# main_multicore.net
KiCad netlist of a schematic drawn in EAGLE
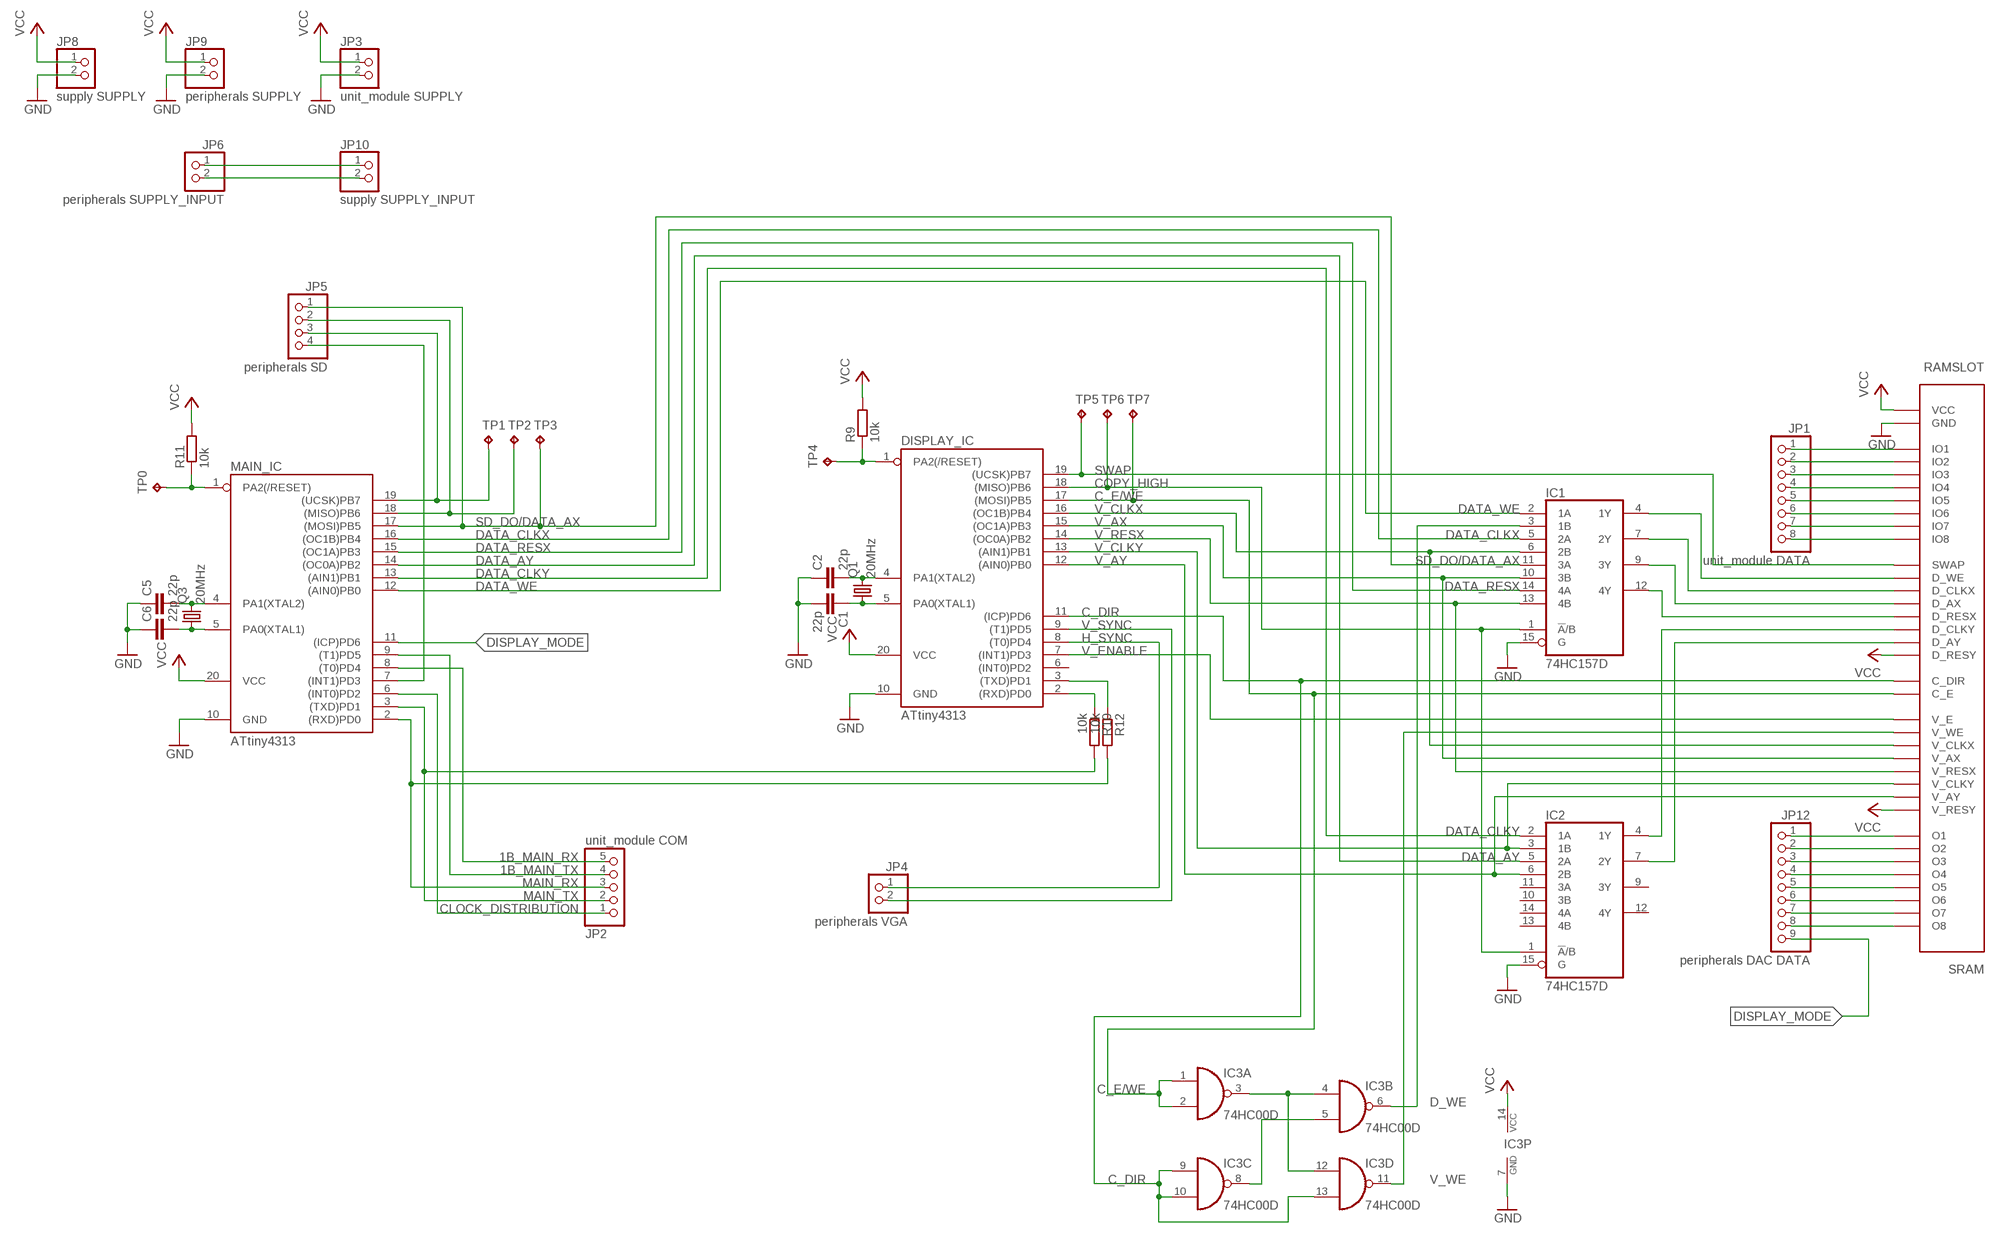
[diagram p0: schematic, sheet 1]

(export (version "E")
  (design (tool "Eeschema 10.0.6"))
  (components
    (comp (ref "C1")
      (value "22p")
      (footprint "eagle-import:C0402")
      (libsource (lib "eagle-import") (part "C-EUC0402"))
    )
    (comp (ref "C2")
      (value "22p")
      (footprint "eagle-import:C0402")
      (libsource (lib "eagle-import") (part "C-EUC0402"))
    )
    (comp (ref "C5")
      (value "22p")
      (footprint "eagle-import:C0402")
      (libsource (lib "eagle-import") (part "C-EUC0402"))
    )
    (comp (ref "C6")
      (value "22p")
      (footprint "eagle-import:C0402")
      (libsource (lib "eagle-import") (part "C-EUC0402"))
    )
    (comp (ref "DISPLAY_IC")
      (value "ATtiny4313")
      (footprint "eagle-import:SO20L$")
      (libsource (lib "eagle-import") (part "TINY2313-S"))
    )
    (comp (ref "IC1")
      (value "74HC157D")
      (footprint "eagle-import:SO16")
      (libsource (lib "eagle-import") (part "74157DHC"))
    )
    (comp (ref "IC2")
      (value "74HC157D")
      (footprint "eagle-import:SO16")
      (libsource (lib "eagle-import") (part "74157DHC"))
    )
    (comp (ref "IC3")
      (value "74HC00D")
      (footprint "eagle-import:SO14")
      (libsource (lib "eagle-import") (part "7400DHC"))
    )
    (comp (ref "JP1")
      (value "unit_module DATA")
      (footprint "eagle-import:1X08")
      (libsource (lib "eagle-import") (part "PINHD-1X8"))
    )
    (comp (ref "JP2")
      (value "unit_module COM")
      (footprint "eagle-import:1X05")
      (libsource (lib "eagle-import") (part "PINHD-1X5"))
    )
    (comp (ref "JP3")
      (value "unit_module SUPPLY")
      (footprint "eagle-import:1X02")
      (libsource (lib "eagle-import") (part "PINHD-1X2"))
    )
    (comp (ref "JP4")
      (value "peripherals VGA")
      (footprint "eagle-import:1X02")
      (libsource (lib "eagle-import") (part "PINHD-1X2"))
    )
    (comp (ref "JP5")
      (value "peripherals SD")
      (footprint "eagle-import:1X04")
      (libsource (lib "eagle-import") (part "PINHD-1X4"))
    )
    (comp (ref "JP6")
      (value "peripherals SUPPLY_INPUT")
      (footprint "eagle-import:1X02")
      (libsource (lib "eagle-import") (part "PINHD-1X2"))
    )
    (comp (ref "JP8")
      (value "supply SUPPLY")
      (footprint "eagle-import:1X02")
      (libsource (lib "eagle-import") (part "PINHD-1X2"))
    )
    (comp (ref "JP9")
      (value "peripherals SUPPLY")
      (footprint "eagle-import:1X02")
      (libsource (lib "eagle-import") (part "PINHD-1X2"))
    )
    (comp (ref "JP10")
      (value "supply SUPPLY_INPUT")
      (footprint "eagle-import:1X02")
      (libsource (lib "eagle-import") (part "PINHD-1X2"))
    )
    (comp (ref "JP12")
      (value "peripherals DAC DATA")
      (footprint "eagle-import:1X09")
      (libsource (lib "eagle-import") (part "PINHD-1X9"))
    )
    (comp (ref "MAIN_IC")
      (value "ATtiny4313")
      (footprint "eagle-import:SO20L$")
      (libsource (lib "eagle-import") (part "TINY2313-S"))
    )
    (comp (ref "Q1")
      (value "20MHz")
      (footprint "eagle-import:MC-405")
      (libsource (lib "eagle-import") (part "MC-405"))
    )
    (comp (ref "Q3")
      (value "20MHz")
      (footprint "eagle-import:MC-405")
      (libsource (lib "eagle-import") (part "MC-405"))
    )
    (comp (ref "R9")
      (value "10k")
      (footprint "eagle-import:R0603")
      (libsource (lib "eagle-import") (part "R-EU_R0603"))
    )
    (comp (ref "R10")
      (value "10k")
      (footprint "eagle-import:R0603")
      (libsource (lib "eagle-import") (part "R-EU_R0603"))
    )
    (comp (ref "R11")
      (value "10k")
      (footprint "eagle-import:R0603")
      (libsource (lib "eagle-import") (part "R-EU_R0603"))
    )
    (comp (ref "R12")
      (value "10k")
      (footprint "eagle-import:R0603")
      (libsource (lib "eagle-import") (part "R-EU_R0603"))
    )
    (comp (ref "RAMSLOT")
      (value "SRAM")
      (footprint "eagle-import:SLOT")
      (libsource (lib "eagle-import") (part "SLOT"))
    )
    (comp (ref "TP0")
      (value "TPB1,27")
      (footprint "eagle-import:B1,27")
      (libsource (lib "eagle-import") (part "TPB1,27"))
    )
    (comp (ref "TP1")
      (value "TPB1,27")
      (footprint "eagle-import:B1,27")
      (libsource (lib "eagle-import") (part "TPB1,27"))
    )
    (comp (ref "TP2")
      (value "TPB1,27")
      (footprint "eagle-import:B1,27")
      (libsource (lib "eagle-import") (part "TPB1,27"))
    )
    (comp (ref "TP3")
      (value "TPB1,27")
      (footprint "eagle-import:B1,27")
      (libsource (lib "eagle-import") (part "TPB1,27"))
    )
    (comp (ref "TP4")
      (value "TPB1,27")
      (footprint "eagle-import:B1,27")
      (libsource (lib "eagle-import") (part "TPB1,27"))
    )
    (comp (ref "TP5")
      (value "TPB1,27")
      (footprint "eagle-import:B1,27")
      (libsource (lib "eagle-import") (part "TPB1,27"))
    )
    (comp (ref "TP6")
      (value "TPB1,27")
      (footprint "eagle-import:B1,27")
      (libsource (lib "eagle-import") (part "TPB1,27"))
    )
    (comp (ref "TP7")
      (value "TPB1,27")
      (footprint "eagle-import:B1,27")
      (libsource (lib "eagle-import") (part "TPB1,27"))
    )
  )
  (nets
    (net (code "1") (name "/1B_MAIN_RX") (class "Default")
      (node (ref "JP2") (pin "5") (pinfunction "5_5") (pintype "passive"))
      (node (ref "MAIN_IC") (pin "8") (pinfunction "(T0)PD4_8") (pintype "bidirectional"))
    )
    (net (code "2") (name "/1B_MAIN_TX") (class "Default")
      (node (ref "JP2") (pin "4") (pinfunction "4_4") (pintype "passive"))
      (node (ref "MAIN_IC") (pin "9") (pinfunction "(T1)PD5_9") (pintype "bidirectional"))
    )
    (net (code "3") (name "/CLOCK_DISTRIBUTION") (class "Default")
      (node (ref "JP2") (pin "1") (pinfunction "1_1") (pintype "passive"))
      (node (ref "MAIN_IC") (pin "6") (pinfunction "(INT0)PD2_6") (pintype "bidirectional"))
    )
    (net (code "4") (name "/COPY_HIGH") (class "Default")
      (node (ref "DISPLAY_IC") (pin "18") (pinfunction "(MISO)PB6_18") (pintype "bidirectional"))
      (node (ref "IC1") (pin "1") (pinfunction "~{A}/B_1") (pintype "input"))
      (node (ref "IC2") (pin "1") (pinfunction "~{A}/B_1") (pintype "input"))
      (node (ref "TP6") (pin "TP") (pinfunction "TP_TP") (pintype "input"))
    )
    (net (code "5") (name "/C_DIR") (class "Default")
      (node (ref "DISPLAY_IC") (pin "11") (pinfunction "(ICP)PD6_11") (pintype "bidirectional"))
      (node (ref "IC3") (pin "10") (pinfunction "I1_10") (pintype "input"))
      (node (ref "IC3") (pin "13") (pinfunction "I1_13") (pintype "input"))
      (node (ref "IC3") (pin "9") (pinfunction "I0_9") (pintype "input"))
      (node (ref "RAMSLOT") (pin "C_DIR") (pinfunction "C_DIR_C_DIR") (pintype "bidirectional"))
    )
    (net (code "6") (name "/C_E{slash}WE") (class "Default")
      (node (ref "DISPLAY_IC") (pin "17") (pinfunction "(MOSI)PB5_17") (pintype "bidirectional"))
      (node (ref "IC3") (pin "1") (pinfunction "I0_1") (pintype "input"))
      (node (ref "IC3") (pin "2") (pinfunction "I1_2") (pintype "input"))
      (node (ref "RAMSLOT") (pin "C_E") (pinfunction "C_E_C_E") (pintype "bidirectional"))
      (node (ref "TP7") (pin "TP") (pinfunction "TP_TP") (pintype "input"))
    )
    (net (code "7") (name "/DATA_AY") (class "Default")
      (node (ref "IC2") (pin "5") (pinfunction "2A_5") (pintype "input"))
      (node (ref "MAIN_IC") (pin "14") (pinfunction "(OC0A)PB2_14") (pintype "bidirectional"))
    )
    (net (code "8") (name "/DATA_CLKX") (class "Default")
      (node (ref "IC1") (pin "5") (pinfunction "2A_5") (pintype "input"))
      (node (ref "MAIN_IC") (pin "16") (pinfunction "(OC1B)PB4_16") (pintype "bidirectional"))
    )
    (net (code "9") (name "/DATA_CLKY") (class "Default")
      (node (ref "IC2") (pin "2") (pinfunction "1A_2") (pintype "input"))
      (node (ref "MAIN_IC") (pin "13") (pinfunction "(AIN1)PB1_13") (pintype "bidirectional"))
    )
    (net (code "10") (name "/DATA_RESX") (class "Default")
      (node (ref "IC1") (pin "14") (pinfunction "4A_14") (pintype "input"))
      (node (ref "MAIN_IC") (pin "15") (pinfunction "(OC1A)PB3_15") (pintype "bidirectional"))
    )
    (net (code "11") (name "/DATA_WE") (class "Default")
      (node (ref "IC1") (pin "2") (pinfunction "1A_2") (pintype "input"))
      (node (ref "MAIN_IC") (pin "12") (pinfunction "(AIN0)PB0_12") (pintype "bidirectional"))
    )
    (net (code "12") (name "/D_WE") (class "Default")
      (node (ref "IC1") (pin "3") (pinfunction "1B_3") (pintype "input"))
      (node (ref "IC3") (pin "6") (pinfunction "O_6") (pintype "output"))
    )
    (net (code "13") (name "/H_SYNC") (class "Default")
      (node (ref "DISPLAY_IC") (pin "8") (pinfunction "(T0)PD4_8") (pintype "bidirectional"))
      (node (ref "JP4") (pin "1") (pinfunction "1_1") (pintype "passive"))
    )
    (net (code "14") (name "/MAIN_RX") (class "Default")
      (node (ref "JP2") (pin "3") (pinfunction "3_3") (pintype "passive"))
      (node (ref "MAIN_IC") (pin "2") (pinfunction "(RXD)PD0_2") (pintype "bidirectional"))
      (node (ref "R12") (pin "2") (pinfunction "2_2") (pintype "passive"))
    )
    (net (code "15") (name "/MAIN_TX") (class "Default")
      (node (ref "JP2") (pin "2") (pinfunction "2_2") (pintype "passive"))
      (node (ref "MAIN_IC") (pin "3") (pinfunction "(TXD)PD1_3") (pintype "bidirectional"))
      (node (ref "R10") (pin "2") (pinfunction "2_2") (pintype "passive"))
    )
    (net (code "16") (name "/SD_DO{slash}DATA_AX") (class "Default")
      (node (ref "IC1") (pin "11") (pinfunction "3A_11") (pintype "input"))
      (node (ref "JP5") (pin "1") (pinfunction "1_1") (pintype "passive"))
      (node (ref "MAIN_IC") (pin "17") (pinfunction "(MOSI)PB5_17") (pintype "bidirectional"))
      (node (ref "TP3") (pin "TP") (pinfunction "TP_TP") (pintype "input"))
    )
    (net (code "17") (name "/SWAP") (class "Default")
      (node (ref "DISPLAY_IC") (pin "19") (pinfunction "(UCSK)PB7_19") (pintype "bidirectional"))
      (node (ref "RAMSLOT") (pin "SWAP") (pinfunction "SWAP_SWAP") (pintype "bidirectional"))
      (node (ref "TP5") (pin "TP") (pinfunction "TP_TP") (pintype "input"))
    )
    (net (code "18") (name "/V_AX") (class "Default")
      (node (ref "DISPLAY_IC") (pin "15") (pinfunction "(OC1A)PB3_15") (pintype "bidirectional"))
      (node (ref "IC1") (pin "10") (pinfunction "3B_10") (pintype "input"))
      (node (ref "RAMSLOT") (pin "V_AX") (pinfunction "V_AX_V_AX") (pintype "bidirectional"))
    )
    (net (code "19") (name "/V_AY") (class "Default")
      (node (ref "DISPLAY_IC") (pin "12") (pinfunction "(AIN0)PB0_12") (pintype "bidirectional"))
      (node (ref "IC2") (pin "6") (pinfunction "2B_6") (pintype "input"))
      (node (ref "RAMSLOT") (pin "V_AY") (pinfunction "V_AY_V_AY") (pintype "bidirectional"))
    )
    (net (code "20") (name "/V_CLKX") (class "Default")
      (node (ref "DISPLAY_IC") (pin "16") (pinfunction "(OC1B)PB4_16") (pintype "bidirectional"))
      (node (ref "IC1") (pin "6") (pinfunction "2B_6") (pintype "input"))
      (node (ref "RAMSLOT") (pin "V_CLKX") (pinfunction "V_CLKX_V_CLKX") (pintype "bidirectional"))
    )
    (net (code "21") (name "/V_CLKY") (class "Default")
      (node (ref "DISPLAY_IC") (pin "13") (pinfunction "(AIN1)PB1_13") (pintype "bidirectional"))
      (node (ref "IC2") (pin "3") (pinfunction "1B_3") (pintype "input"))
      (node (ref "RAMSLOT") (pin "V_CLKY") (pinfunction "V_CLKY_V_CLKY") (pintype "bidirectional"))
    )
    (net (code "22") (name "/V_ENABLE") (class "Default")
      (node (ref "DISPLAY_IC") (pin "7") (pinfunction "(INT1)PD3_7") (pintype "bidirectional"))
      (node (ref "RAMSLOT") (pin "V_E") (pinfunction "V_E_V_E") (pintype "bidirectional"))
    )
    (net (code "23") (name "/V_RESX") (class "Default")
      (node (ref "DISPLAY_IC") (pin "14") (pinfunction "(OC0A)PB2_14") (pintype "bidirectional"))
      (node (ref "IC1") (pin "13") (pinfunction "4B_13") (pintype "input"))
      (node (ref "RAMSLOT") (pin "V_RESX") (pinfunction "V_RESX_V_RESX") (pintype "bidirectional"))
    )
    (net (code "24") (name "/V_SYNC") (class "Default")
      (node (ref "DISPLAY_IC") (pin "9") (pinfunction "(T1)PD5_9") (pintype "bidirectional"))
      (node (ref "JP4") (pin "2") (pinfunction "2_2") (pintype "passive"))
    )
    (net (code "25") (name "/V_WE") (class "Default")
      (node (ref "IC3") (pin "11") (pinfunction "O_11") (pintype "output"))
      (node (ref "RAMSLOT") (pin "V_WE") (pinfunction "V_WE_V_WE") (pintype "bidirectional"))
    )
    (net (code "26") (name "DISPLAY_MODE") (class "Default")
      (node (ref "JP12") (pin "9") (pinfunction "9_9") (pintype "passive"))
      (node (ref "MAIN_IC") (pin "11") (pinfunction "(ICP)PD6_11") (pintype "bidirectional"))
    )
    (net (code "27") (name "GND") (class "Default")
      (node (ref "C1") (pin "2") (pinfunction "2_2") (pintype "passive"))
      (node (ref "C2") (pin "1") (pinfunction "1_1") (pintype "passive"))
      (node (ref "C5") (pin "1") (pinfunction "1_1") (pintype "passive"))
      (node (ref "C6") (pin "1") (pinfunction "1_1") (pintype "passive"))
      (node (ref "DISPLAY_IC") (pin "10") (pinfunction "GND_10") (pintype "power_in"))
      (node (ref "IC1") (pin "15") (pinfunction "G_15") (pintype "input"))
      (node (ref "IC2") (pin "15") (pinfunction "G_15") (pintype "input"))
      (node (ref "IC3") (pin "7") (pinfunction "GND_7") (pintype "power_in"))
      (node (ref "JP3") (pin "2") (pinfunction "2_2") (pintype "passive"))
      (node (ref "JP8") (pin "2") (pinfunction "2_2") (pintype "passive"))
      (node (ref "JP9") (pin "2") (pinfunction "2_2") (pintype "passive"))
      (node (ref "MAIN_IC") (pin "10") (pinfunction "GND_10") (pintype "power_in"))
      (node (ref "RAMSLOT") (pin "GND") (pinfunction "GND_GND") (pintype "bidirectional"))
    )
    (net (code "28") (name "Net-(DISPLAY_IC-(RXD)PD0)") (class "Default")
      (node (ref "DISPLAY_IC") (pin "2") (pinfunction "(RXD)PD0_2") (pintype "bidirectional"))
      (node (ref "R10") (pin "1") (pinfunction "1_1") (pintype "passive"))
    )
    (net (code "29") (name "Net-(DISPLAY_IC-(TXD)PD1)") (class "Default")
      (node (ref "DISPLAY_IC") (pin "3") (pinfunction "(TXD)PD1_3") (pintype "bidirectional"))
      (node (ref "R12") (pin "1") (pinfunction "1_1") (pintype "passive"))
    )
    (net (code "30") (name "Net-(DISPLAY_IC-PA0(XTAL1))") (class "Default")
      (node (ref "C1") (pin "1") (pinfunction "1_1") (pintype "passive"))
      (node (ref "DISPLAY_IC") (pin "5") (pinfunction "PA0(XTAL1)_5") (pintype "bidirectional"))
      (node (ref "Q1") (pin "1") (pinfunction "1_1") (pintype "passive"))
    )
    (net (code "31") (name "Net-(DISPLAY_IC-PA1(XTAL2))") (class "Default")
      (node (ref "C2") (pin "2") (pinfunction "2_2") (pintype "passive"))
      (node (ref "DISPLAY_IC") (pin "4") (pinfunction "PA1(XTAL2)_4") (pintype "bidirectional"))
      (node (ref "Q1") (pin "2") (pinfunction "2_2") (pintype "passive"))
    )
    (net (code "32") (name "Net-(DISPLAY_IC-PA2({slash}RESET))") (class "Default")
      (node (ref "DISPLAY_IC") (pin "1") (pinfunction "PA2(/RESET)_1") (pintype "input"))
      (node (ref "R9") (pin "1") (pinfunction "1_1") (pintype "passive"))
      (node (ref "TP4") (pin "TP") (pinfunction "TP_TP") (pintype "input"))
    )
    (net (code "33") (name "Net-(IC1A-1Y)") (class "Default")
      (node (ref "IC1") (pin "4") (pinfunction "1Y_4") (pintype "output"))
      (node (ref "RAMSLOT") (pin "D_WE") (pinfunction "D_WE_D_WE") (pintype "bidirectional"))
    )
    (net (code "34") (name "Net-(IC1A-2Y)") (class "Default")
      (node (ref "IC1") (pin "7") (pinfunction "2Y_7") (pintype "output"))
      (node (ref "RAMSLOT") (pin "D_CLKX") (pinfunction "D_CLKX_D_CLKX") (pintype "bidirectional"))
    )
    (net (code "35") (name "Net-(IC1A-3Y)") (class "Default")
      (node (ref "IC1") (pin "9") (pinfunction "3Y_9") (pintype "output"))
      (node (ref "RAMSLOT") (pin "D_AX") (pinfunction "D_AX_D_AX") (pintype "bidirectional"))
    )
    (net (code "36") (name "Net-(IC1A-4Y)") (class "Default")
      (node (ref "IC1") (pin "12") (pinfunction "4Y_12") (pintype "output"))
      (node (ref "RAMSLOT") (pin "D_RESX") (pinfunction "D_RESX_D_RESX") (pintype "bidirectional"))
    )
    (net (code "37") (name "Net-(IC2A-1Y)") (class "Default")
      (node (ref "IC2") (pin "4") (pinfunction "1Y_4") (pintype "output"))
      (node (ref "RAMSLOT") (pin "D_CLKY") (pinfunction "D_CLKY_D_CLKY") (pintype "bidirectional"))
    )
    (net (code "38") (name "Net-(IC2A-2Y)") (class "Default")
      (node (ref "IC2") (pin "7") (pinfunction "2Y_7") (pintype "output"))
      (node (ref "RAMSLOT") (pin "D_AY") (pinfunction "D_AY_D_AY") (pintype "bidirectional"))
    )
    (net (code "39") (name "Net-(IC3A-O)") (class "Default")
      (node (ref "IC3") (pin "12") (pinfunction "I0_12") (pintype "input"))
      (node (ref "IC3") (pin "3") (pinfunction "O_3") (pintype "output"))
      (node (ref "IC3") (pin "4") (pinfunction "I0_4") (pintype "input"))
    )
    (net (code "40") (name "Net-(IC3B-I1)") (class "Default")
      (node (ref "IC3") (pin "5") (pinfunction "I1_5") (pintype "input"))
      (node (ref "IC3") (pin "8") (pinfunction "O_8") (pintype "output"))
    )
    (net (code "41") (name "Net-(JP1-Pad1)") (class "Default")
      (node (ref "JP1") (pin "1") (pinfunction "1_1") (pintype "passive"))
      (node (ref "RAMSLOT") (pin "IO1") (pinfunction "IO1_IO1") (pintype "bidirectional"))
    )
    (net (code "42") (name "Net-(JP1-Pad2)") (class "Default")
      (node (ref "JP1") (pin "2") (pinfunction "2_2") (pintype "passive"))
      (node (ref "RAMSLOT") (pin "IO2") (pinfunction "IO2_IO2") (pintype "bidirectional"))
    )
    (net (code "43") (name "Net-(JP1-Pad3)") (class "Default")
      (node (ref "JP1") (pin "3") (pinfunction "3_3") (pintype "passive"))
      (node (ref "RAMSLOT") (pin "IO3") (pinfunction "IO3_IO3") (pintype "bidirectional"))
    )
    (net (code "44") (name "Net-(JP1-Pad4)") (class "Default")
      (node (ref "JP1") (pin "4") (pinfunction "4_4") (pintype "passive"))
      (node (ref "RAMSLOT") (pin "IO4") (pinfunction "IO4_IO4") (pintype "bidirectional"))
    )
    (net (code "45") (name "Net-(JP1-Pad5)") (class "Default")
      (node (ref "JP1") (pin "5") (pinfunction "5_5") (pintype "passive"))
      (node (ref "RAMSLOT") (pin "IO5") (pinfunction "IO5_IO5") (pintype "bidirectional"))
    )
    (net (code "46") (name "Net-(JP1-Pad6)") (class "Default")
      (node (ref "JP1") (pin "6") (pinfunction "6_6") (pintype "passive"))
      (node (ref "RAMSLOT") (pin "IO6") (pinfunction "IO6_IO6") (pintype "bidirectional"))
    )
    (net (code "47") (name "Net-(JP1-Pad7)") (class "Default")
      (node (ref "JP1") (pin "7") (pinfunction "7_7") (pintype "passive"))
      (node (ref "RAMSLOT") (pin "IO7") (pinfunction "IO7_IO7") (pintype "bidirectional"))
    )
    (net (code "48") (name "Net-(JP1-Pad8)") (class "Default")
      (node (ref "JP1") (pin "8") (pinfunction "8_8") (pintype "passive"))
      (node (ref "RAMSLOT") (pin "IO8") (pinfunction "IO8_IO8") (pintype "bidirectional"))
    )
    (net (code "49") (name "Net-(JP10-Pad1)") (class "Default")
      (node (ref "JP10") (pin "1") (pinfunction "1_1") (pintype "passive"))
      (node (ref "JP6") (pin "1") (pinfunction "1_1") (pintype "passive"))
    )
    (net (code "50") (name "Net-(JP10-Pad2)") (class "Default")
      (node (ref "JP10") (pin "2") (pinfunction "2_2") (pintype "passive"))
      (node (ref "JP6") (pin "2") (pinfunction "2_2") (pintype "passive"))
    )
    (net (code "51") (name "Net-(JP12-Pad1)") (class "Default")
      (node (ref "JP12") (pin "1") (pinfunction "1_1") (pintype "passive"))
      (node (ref "RAMSLOT") (pin "O1") (pinfunction "O1_O1") (pintype "bidirectional"))
    )
    (net (code "52") (name "Net-(JP12-Pad2)") (class "Default")
      (node (ref "JP12") (pin "2") (pinfunction "2_2") (pintype "passive"))
      (node (ref "RAMSLOT") (pin "O2") (pinfunction "O2_O2") (pintype "bidirectional"))
    )
    (net (code "53") (name "Net-(JP12-Pad3)") (class "Default")
      (node (ref "JP12") (pin "3") (pinfunction "3_3") (pintype "passive"))
      (node (ref "RAMSLOT") (pin "O3") (pinfunction "O3_O3") (pintype "bidirectional"))
    )
    (net (code "54") (name "Net-(JP12-Pad4)") (class "Default")
      (node (ref "JP12") (pin "4") (pinfunction "4_4") (pintype "passive"))
      (node (ref "RAMSLOT") (pin "O4") (pinfunction "O4_O4") (pintype "bidirectional"))
    )
    (net (code "55") (name "Net-(JP12-Pad5)") (class "Default")
      (node (ref "JP12") (pin "5") (pinfunction "5_5") (pintype "passive"))
      (node (ref "RAMSLOT") (pin "O5") (pinfunction "O5_O5") (pintype "bidirectional"))
    )
    (net (code "56") (name "Net-(JP12-Pad6)") (class "Default")
      (node (ref "JP12") (pin "6") (pinfunction "6_6") (pintype "passive"))
      (node (ref "RAMSLOT") (pin "O6") (pinfunction "O6_O6") (pintype "bidirectional"))
    )
    (net (code "57") (name "Net-(JP12-Pad7)") (class "Default")
      (node (ref "JP12") (pin "7") (pinfunction "7_7") (pintype "passive"))
      (node (ref "RAMSLOT") (pin "O7") (pinfunction "O7_O7") (pintype "bidirectional"))
    )
    (net (code "58") (name "Net-(JP12-Pad8)") (class "Default")
      (node (ref "JP12") (pin "8") (pinfunction "8_8") (pintype "passive"))
      (node (ref "RAMSLOT") (pin "O8") (pinfunction "O8_O8") (pintype "bidirectional"))
    )
    (net (code "59") (name "Net-(MAIN_IC-(INT1)PD3)") (class "Default")
      (node (ref "JP5") (pin "4") (pinfunction "4_4") (pintype "passive"))
      (node (ref "MAIN_IC") (pin "7") (pinfunction "(INT1)PD3_7") (pintype "bidirectional"))
    )
    (net (code "60") (name "Net-(MAIN_IC-(MISO)PB6)") (class "Default")
      (node (ref "JP5") (pin "2") (pinfunction "2_2") (pintype "passive"))
      (node (ref "MAIN_IC") (pin "18") (pinfunction "(MISO)PB6_18") (pintype "bidirectional"))
      (node (ref "TP2") (pin "TP") (pinfunction "TP_TP") (pintype "input"))
    )
    (net (code "61") (name "Net-(MAIN_IC-(UCSK)PB7)") (class "Default")
      (node (ref "JP5") (pin "3") (pinfunction "3_3") (pintype "passive"))
      (node (ref "MAIN_IC") (pin "19") (pinfunction "(UCSK)PB7_19") (pintype "bidirectional"))
      (node (ref "TP1") (pin "TP") (pinfunction "TP_TP") (pintype "input"))
    )
    (net (code "62") (name "Net-(MAIN_IC-PA0(XTAL1))") (class "Default")
      (node (ref "C6") (pin "2") (pinfunction "2_2") (pintype "passive"))
      (node (ref "MAIN_IC") (pin "5") (pinfunction "PA0(XTAL1)_5") (pintype "bidirectional"))
      (node (ref "Q3") (pin "1") (pinfunction "1_1") (pintype "passive"))
    )
    (net (code "63") (name "Net-(MAIN_IC-PA1(XTAL2))") (class "Default")
      (node (ref "C5") (pin "2") (pinfunction "2_2") (pintype "passive"))
      (node (ref "MAIN_IC") (pin "4") (pinfunction "PA1(XTAL2)_4") (pintype "bidirectional"))
      (node (ref "Q3") (pin "2") (pinfunction "2_2") (pintype "passive"))
    )
    (net (code "64") (name "Net-(MAIN_IC-PA2({slash}RESET))") (class "Default")
      (node (ref "MAIN_IC") (pin "1") (pinfunction "PA2(/RESET)_1") (pintype "input"))
      (node (ref "R11") (pin "1") (pinfunction "1_1") (pintype "passive"))
      (node (ref "TP0") (pin "TP") (pinfunction "TP_TP") (pintype "input"))
    )
    (net (code "65") (name "VCC") (class "Default")
      (node (ref "DISPLAY_IC") (pin "20") (pinfunction "VCC_20") (pintype "power_in"))
      (node (ref "IC3") (pin "14") (pinfunction "VCC_14") (pintype "power_in"))
      (node (ref "JP3") (pin "1") (pinfunction "1_1") (pintype "passive"))
      (node (ref "JP8") (pin "1") (pinfunction "1_1") (pintype "passive"))
      (node (ref "JP9") (pin "1") (pinfunction "1_1") (pintype "passive"))
      (node (ref "MAIN_IC") (pin "20") (pinfunction "VCC_20") (pintype "power_in"))
      (node (ref "R11") (pin "2") (pinfunction "2_2") (pintype "passive"))
      (node (ref "R9") (pin "2") (pinfunction "2_2") (pintype "passive"))
      (node (ref "RAMSLOT") (pin "D_RESY") (pinfunction "D_RESY_D_RESY") (pintype "bidirectional"))
      (node (ref "RAMSLOT") (pin "VCC") (pinfunction "VCC_VCC") (pintype "bidirectional"))
      (node (ref "RAMSLOT") (pin "V_RESY") (pinfunction "V_RESY_V_RESY") (pintype "bidirectional"))
    )
    (net (code "66") (name "unconnected-(DISPLAY_IC-(INT0)PD2-Pad6)") (class "Default")
      (node (ref "DISPLAY_IC") (pin "6") (pinfunction "(INT0)PD2_6") (pintype "bidirectional"))
    )
    (net (code "67") (name "unconnected-(IC2A-3A-Pad11)") (class "Default")
      (node (ref "IC2") (pin "11") (pinfunction "3A_11") (pintype "input"))
    )
    (net (code "68") (name "unconnected-(IC2A-3B-Pad10)") (class "Default")
      (node (ref "IC2") (pin "10") (pinfunction "3B_10") (pintype "input"))
    )
    (net (code "69") (name "unconnected-(IC2A-3Y-Pad9)") (class "Default")
      (node (ref "IC2") (pin "9") (pinfunction "3Y_9") (pintype "output"))
    )
    (net (code "70") (name "unconnected-(IC2A-4A-Pad14)") (class "Default")
      (node (ref "IC2") (pin "14") (pinfunction "4A_14") (pintype "input"))
    )
    (net (code "71") (name "unconnected-(IC2A-4B-Pad13)") (class "Default")
      (node (ref "IC2") (pin "13") (pinfunction "4B_13") (pintype "input"))
    )
    (net (code "72") (name "unconnected-(IC2A-4Y-Pad12)") (class "Default")
      (node (ref "IC2") (pin "12") (pinfunction "4Y_12") (pintype "output"))
    )
  )
)
